# upper-pcb.net
KiCad netlist of a schematic drawn in Altium Designer
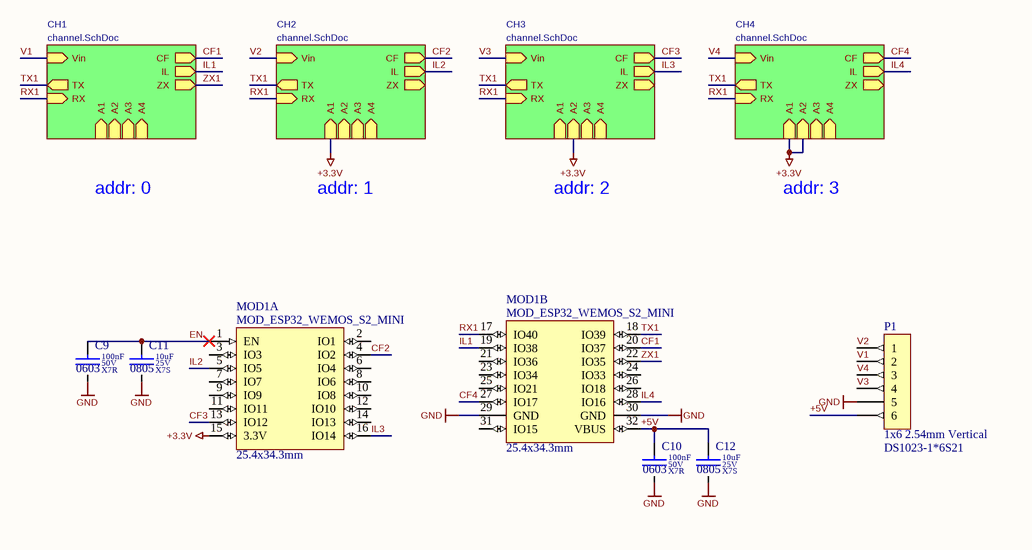
[diagram p0: upper-pcb.SchDoc]

(export (version "E")
  (design (tool "Eeschema 10.0.6"))
  (components
    (comp (ref "C9")
      (value "100nF")
      (footprint "C_0603_1608")
      (description "Capacitor")
      (fields
        (field (name "DIELECTRIC") "X7R")
        (field (name "VOLTAGE") "50V")
        (field (name "SCH_FOOTPRINT") "0603")
        (field (name "PART NUMBER") "C_100nF_50V_X7R_0603_5")
        (field (name "MANUFACTURER") "Samsung")
      )
      (libsource (lib "Library") (part "C"))
    )
    (comp (ref "C10")
      (value "100nF")
      (footprint "C_0603_1608")
      (description "Capacitor")
      (fields
        (field (name "DIELECTRIC") "X7R")
        (field (name "VOLTAGE") "50V")
        (field (name "SCH_FOOTPRINT") "0603")
        (field (name "PART NUMBER") "C_100nF_50V_X7R_0603_5")
        (field (name "MANUFACTURER") "Samsung")
      )
      (libsource (lib "Library") (part "C"))
    )
    (comp (ref "C11")
      (value "10uF")
      (footprint "C_0805_2012")
      (description "Capacitor")
      (fields
        (field (name "DIELECTRIC") "X7S")
        (field (name "VOLTAGE") "25V")
        (field (name "SCH_FOOTPRINT") "0805")
        (field (name "PART NUMBER") "C_10uF_25V_X7S_0805_10")
        (field (name "MANUFACTURER") "Murata")
      )
      (libsource (lib "Library") (part "C"))
    )
    (comp (ref "C12")
      (value "10uF")
      (footprint "C_0805_2012")
      (description "Capacitor")
      (fields
        (field (name "DIELECTRIC") "X7S")
        (field (name "VOLTAGE") "25V")
        (field (name "SCH_FOOTPRINT") "0805")
        (field (name "PART NUMBER") "C_10uF_25V_X7S_0805_10")
        (field (name "MANUFACTURER") "Murata")
      )
      (libsource (lib "Library") (part "C"))
    )
    (comp (ref "MOD1")
      (value "MOD_ESP32_WEMOS_S2_MINI")
      (footprint "MOD_ESP32_WEMOS_S2_MINI")
      (fields
        (field (name "SCH_FOOTPRINT") "25.4x34.3mm")
        (field (name "MANUFACTURER") "Wemos")
        (field (name "Comment") "ESP32-S2FN4R2 mini wifi board")
      )
      (libsource (lib "Library") (part "MOD_ESP32_WEMOS_S2_MINI"))
    )
    (comp (ref "P1")
      (value "DS1023-1*6S21")
      (footprint "J_HEADER_1x6_2.54_VERTICAL")
      (description "Pin Header")
      (fields
        (field (name "SCH_FOOTPRINT") "1x6 2.54mm Vertical")
        (field (name "PART NUMBER") "J_HEADER_1x6_2.54_VERTICAL")
        (field (name "MANUFACTURER") "Connfly")
      )
      (libsource (lib "Library") (part "J_HEADER_1x6"))
    )
  )
  (nets
    (net (code "1") (name "+3.3V") (class "Default")
      (node (ref "MOD1") (pin "15") (pinfunction "3.3V_15") (pintype "bidirectional"))
    )
    (net (code "2") (name "/+5V") (class "Default")
      (node (ref "C10") (pin "1") (pinfunction "1_1") (pintype "passive"))
      (node (ref "C12") (pin "1") (pinfunction "1_1") (pintype "passive"))
      (node (ref "MOD1") (pin "32") (pinfunction "VBUS_32") (pintype "bidirectional"))
      (node (ref "P1") (pin "6") (pinfunction "6_6") (pintype "output"))
    )
    (net (code "15") (name "/CF1") (class "Default")
      (node (ref "MOD1") (pin "20") (pinfunction "IO37_20") (pintype "bidirectional"))
    )
    (net (code "16") (name "/CF2") (class "Default")
      (node (ref "MOD1") (pin "4") (pinfunction "IO2_4") (pintype "bidirectional"))
    )
    (net (code "17") (name "/CF3") (class "Default")
      (node (ref "MOD1") (pin "13") (pinfunction "IO12_13") (pintype "bidirectional"))
    )
    (net (code "18") (name "/CF4") (class "Default")
      (node (ref "MOD1") (pin "27") (pinfunction "IO17_27") (pintype "bidirectional"))
    )
    (net (code "19") (name "/EN") (class "Default")
      (node (ref "C11") (pin "1") (pinfunction "1_1") (pintype "passive"))
      (node (ref "C9") (pin "1") (pinfunction "1_1") (pintype "passive"))
      (node (ref "MOD1") (pin "1") (pinfunction "EN_1") (pintype "input"))
    )
    (net (code "20") (name "/IL1") (class "Default")
      (node (ref "MOD1") (pin "19") (pinfunction "IO38_19") (pintype "bidirectional"))
    )
    (net (code "21") (name "/IL2") (class "Default")
      (node (ref "MOD1") (pin "5") (pinfunction "IO5_5") (pintype "bidirectional"))
    )
    (net (code "22") (name "/IL3") (class "Default")
      (node (ref "MOD1") (pin "16") (pinfunction "IO14_16") (pintype "bidirectional"))
    )
    (net (code "23") (name "/IL4") (class "Default")
      (node (ref "MOD1") (pin "28") (pinfunction "IO16_28") (pintype "bidirectional"))
    )
    (net (code "24") (name "/RX1") (class "Default")
      (node (ref "MOD1") (pin "17") (pinfunction "IO40_17") (pintype "bidirectional"))
    )
    (net (code "25") (name "/TX1") (class "Default")
      (node (ref "MOD1") (pin "18") (pinfunction "IO39_18") (pintype "bidirectional"))
    )
    (net (code "26") (name "/V1") (class "Default")
      (node (ref "P1") (pin "2") (pinfunction "2_2") (pintype "output"))
    )
    (net (code "27") (name "/V2") (class "Default")
      (node (ref "P1") (pin "1") (pinfunction "1_1") (pintype "output"))
    )
    (net (code "28") (name "/V3") (class "Default")
      (node (ref "P1") (pin "4") (pinfunction "4_4") (pintype "output"))
    )
    (net (code "29") (name "/V4") (class "Default")
      (node (ref "P1") (pin "3") (pinfunction "3_3") (pintype "output"))
    )
    (net (code "31") (name "/ZX1") (class "Default")
      (node (ref "MOD1") (pin "22") (pinfunction "IO35_22") (pintype "bidirectional"))
    )
    (net (code "34") (name "GND") (class "Default")
      (node (ref "C10") (pin "2") (pinfunction "2_2") (pintype "passive"))
      (node (ref "C11") (pin "2") (pinfunction "2_2") (pintype "passive"))
      (node (ref "C12") (pin "2") (pinfunction "2_2") (pintype "passive"))
      (node (ref "C9") (pin "2") (pinfunction "2_2") (pintype "passive"))
      (node (ref "MOD1") (pin "29") (pinfunction "GND_29") (pintype "power_in"))
      (node (ref "MOD1") (pin "30") (pinfunction "GND_30") (pintype "power_in"))
      (node (ref "P1") (pin "5") (pinfunction "5_5") (pintype "passive"))
    )
    (net (code "35") (name "unconnected-(MOD1A-IO1-Pad2)") (class "Default")
      (node (ref "MOD1") (pin "2") (pinfunction "IO1_2") (pintype "bidirectional"))
    )
    (net (code "36") (name "unconnected-(MOD1A-IO3-Pad3)") (class "Default")
      (node (ref "MOD1") (pin "3") (pinfunction "IO3_3") (pintype "bidirectional"))
    )
    (net (code "37") (name "unconnected-(MOD1A-IO4-Pad6)") (class "Default")
      (node (ref "MOD1") (pin "6") (pinfunction "IO4_6") (pintype "bidirectional"))
    )
    (net (code "38") (name "unconnected-(MOD1A-IO6-Pad8)") (class "Default")
      (node (ref "MOD1") (pin "8") (pinfunction "IO6_8") (pintype "bidirectional"))
    )
    (net (code "39") (name "unconnected-(MOD1A-IO7-Pad7)") (class "Default")
      (node (ref "MOD1") (pin "7") (pinfunction "IO7_7") (pintype "bidirectional"))
    )
    (net (code "40") (name "unconnected-(MOD1A-IO8-Pad10)") (class "Default")
      (node (ref "MOD1") (pin "10") (pinfunction "IO8_10") (pintype "bidirectional"))
    )
    (net (code "41") (name "unconnected-(MOD1A-IO9-Pad9)") (class "Default")
      (node (ref "MOD1") (pin "9") (pinfunction "IO9_9") (pintype "bidirectional"))
    )
    (net (code "42") (name "unconnected-(MOD1A-IO10-Pad12)") (class "Default")
      (node (ref "MOD1") (pin "12") (pinfunction "IO10_12") (pintype "bidirectional"))
    )
    (net (code "43") (name "unconnected-(MOD1A-IO11-Pad11)") (class "Default")
      (node (ref "MOD1") (pin "11") (pinfunction "IO11_11") (pintype "bidirectional"))
    )
    (net (code "44") (name "unconnected-(MOD1A-IO13-Pad14)") (class "Default")
      (node (ref "MOD1") (pin "14") (pinfunction "IO13_14") (pintype "bidirectional"))
    )
    (net (code "45") (name "unconnected-(MOD1B-IO15-Pad31)") (class "Default")
      (node (ref "MOD1") (pin "31") (pinfunction "IO15_31") (pintype "bidirectional"))
    )
    (net (code "46") (name "unconnected-(MOD1B-IO18-Pad26)") (class "Default")
      (node (ref "MOD1") (pin "26") (pinfunction "IO18_26") (pintype "bidirectional"))
    )
    (net (code "47") (name "unconnected-(MOD1B-IO21-Pad25)") (class "Default")
      (node (ref "MOD1") (pin "25") (pinfunction "IO21_25") (pintype "bidirectional"))
    )
    (net (code "48") (name "unconnected-(MOD1B-IO33-Pad24)") (class "Default")
      (node (ref "MOD1") (pin "24") (pinfunction "IO33_24") (pintype "bidirectional"))
    )
    (net (code "49") (name "unconnected-(MOD1B-IO34-Pad23)") (class "Default")
      (node (ref "MOD1") (pin "23") (pinfunction "IO34_23") (pintype "bidirectional"))
    )
    (net (code "50") (name "unconnected-(MOD1B-IO36-Pad21)") (class "Default")
      (node (ref "MOD1") (pin "21") (pinfunction "IO36_21") (pintype "bidirectional"))
    )
  )
)
